# single_horz_wth_para.net
KiCad netlist of a schematic drawn in EAGLE
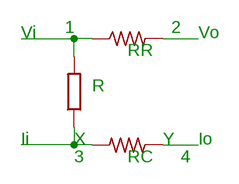
[diagram p0: schematic, sheet 1]

(export (version "E")
  (design (tool "Eeschema 10.0.6"))
  (components
    (comp (ref "R")
      (value "R-EU_0204/2V")
      (footprint "eagle-import:0204V")
      (libsource (lib "eagle-import") (part "R-EU_0204/2V"))
    )
    (comp (ref "RC")
      (value "R-US_0204/2V")
      (footprint "eagle-import:0204V")
      (libsource (lib "eagle-import") (part "R-US_0204/2V"))
    )
    (comp (ref "RR")
      (value "R-US_0204/2V")
      (footprint "eagle-import:0204V")
      (libsource (lib "eagle-import") (part "R-US_0204/2V"))
    )
  )
  (nets
    (net (code "1") (name "Net-(R-Pad1)") (class "Default")
      (node (ref "R") (pin "1") (pinfunction "1_1") (pintype "passive"))
      (node (ref "RC") (pin "2") (pinfunction "2_2") (pintype "passive"))
    )
    (net (code "2") (name "Net-(R-Pad2)") (class "Default")
      (node (ref "R") (pin "2") (pinfunction "2_2") (pintype "passive"))
      (node (ref "RR") (pin "1") (pinfunction "1_1") (pintype "passive"))
    )
    (net (code "3") (name "unconnected-(RC-Pad1)") (class "Default")
      (node (ref "RC") (pin "1") (pinfunction "1_1") (pintype "passive"))
    )
    (net (code "4") (name "unconnected-(RR-Pad2)") (class "Default")
      (node (ref "RR") (pin "2") (pinfunction "2_2") (pintype "passive"))
    )
  )
)
